# solar_panel_5v.net
KiCad netlist of a schematic drawn in EasyEDA Pro
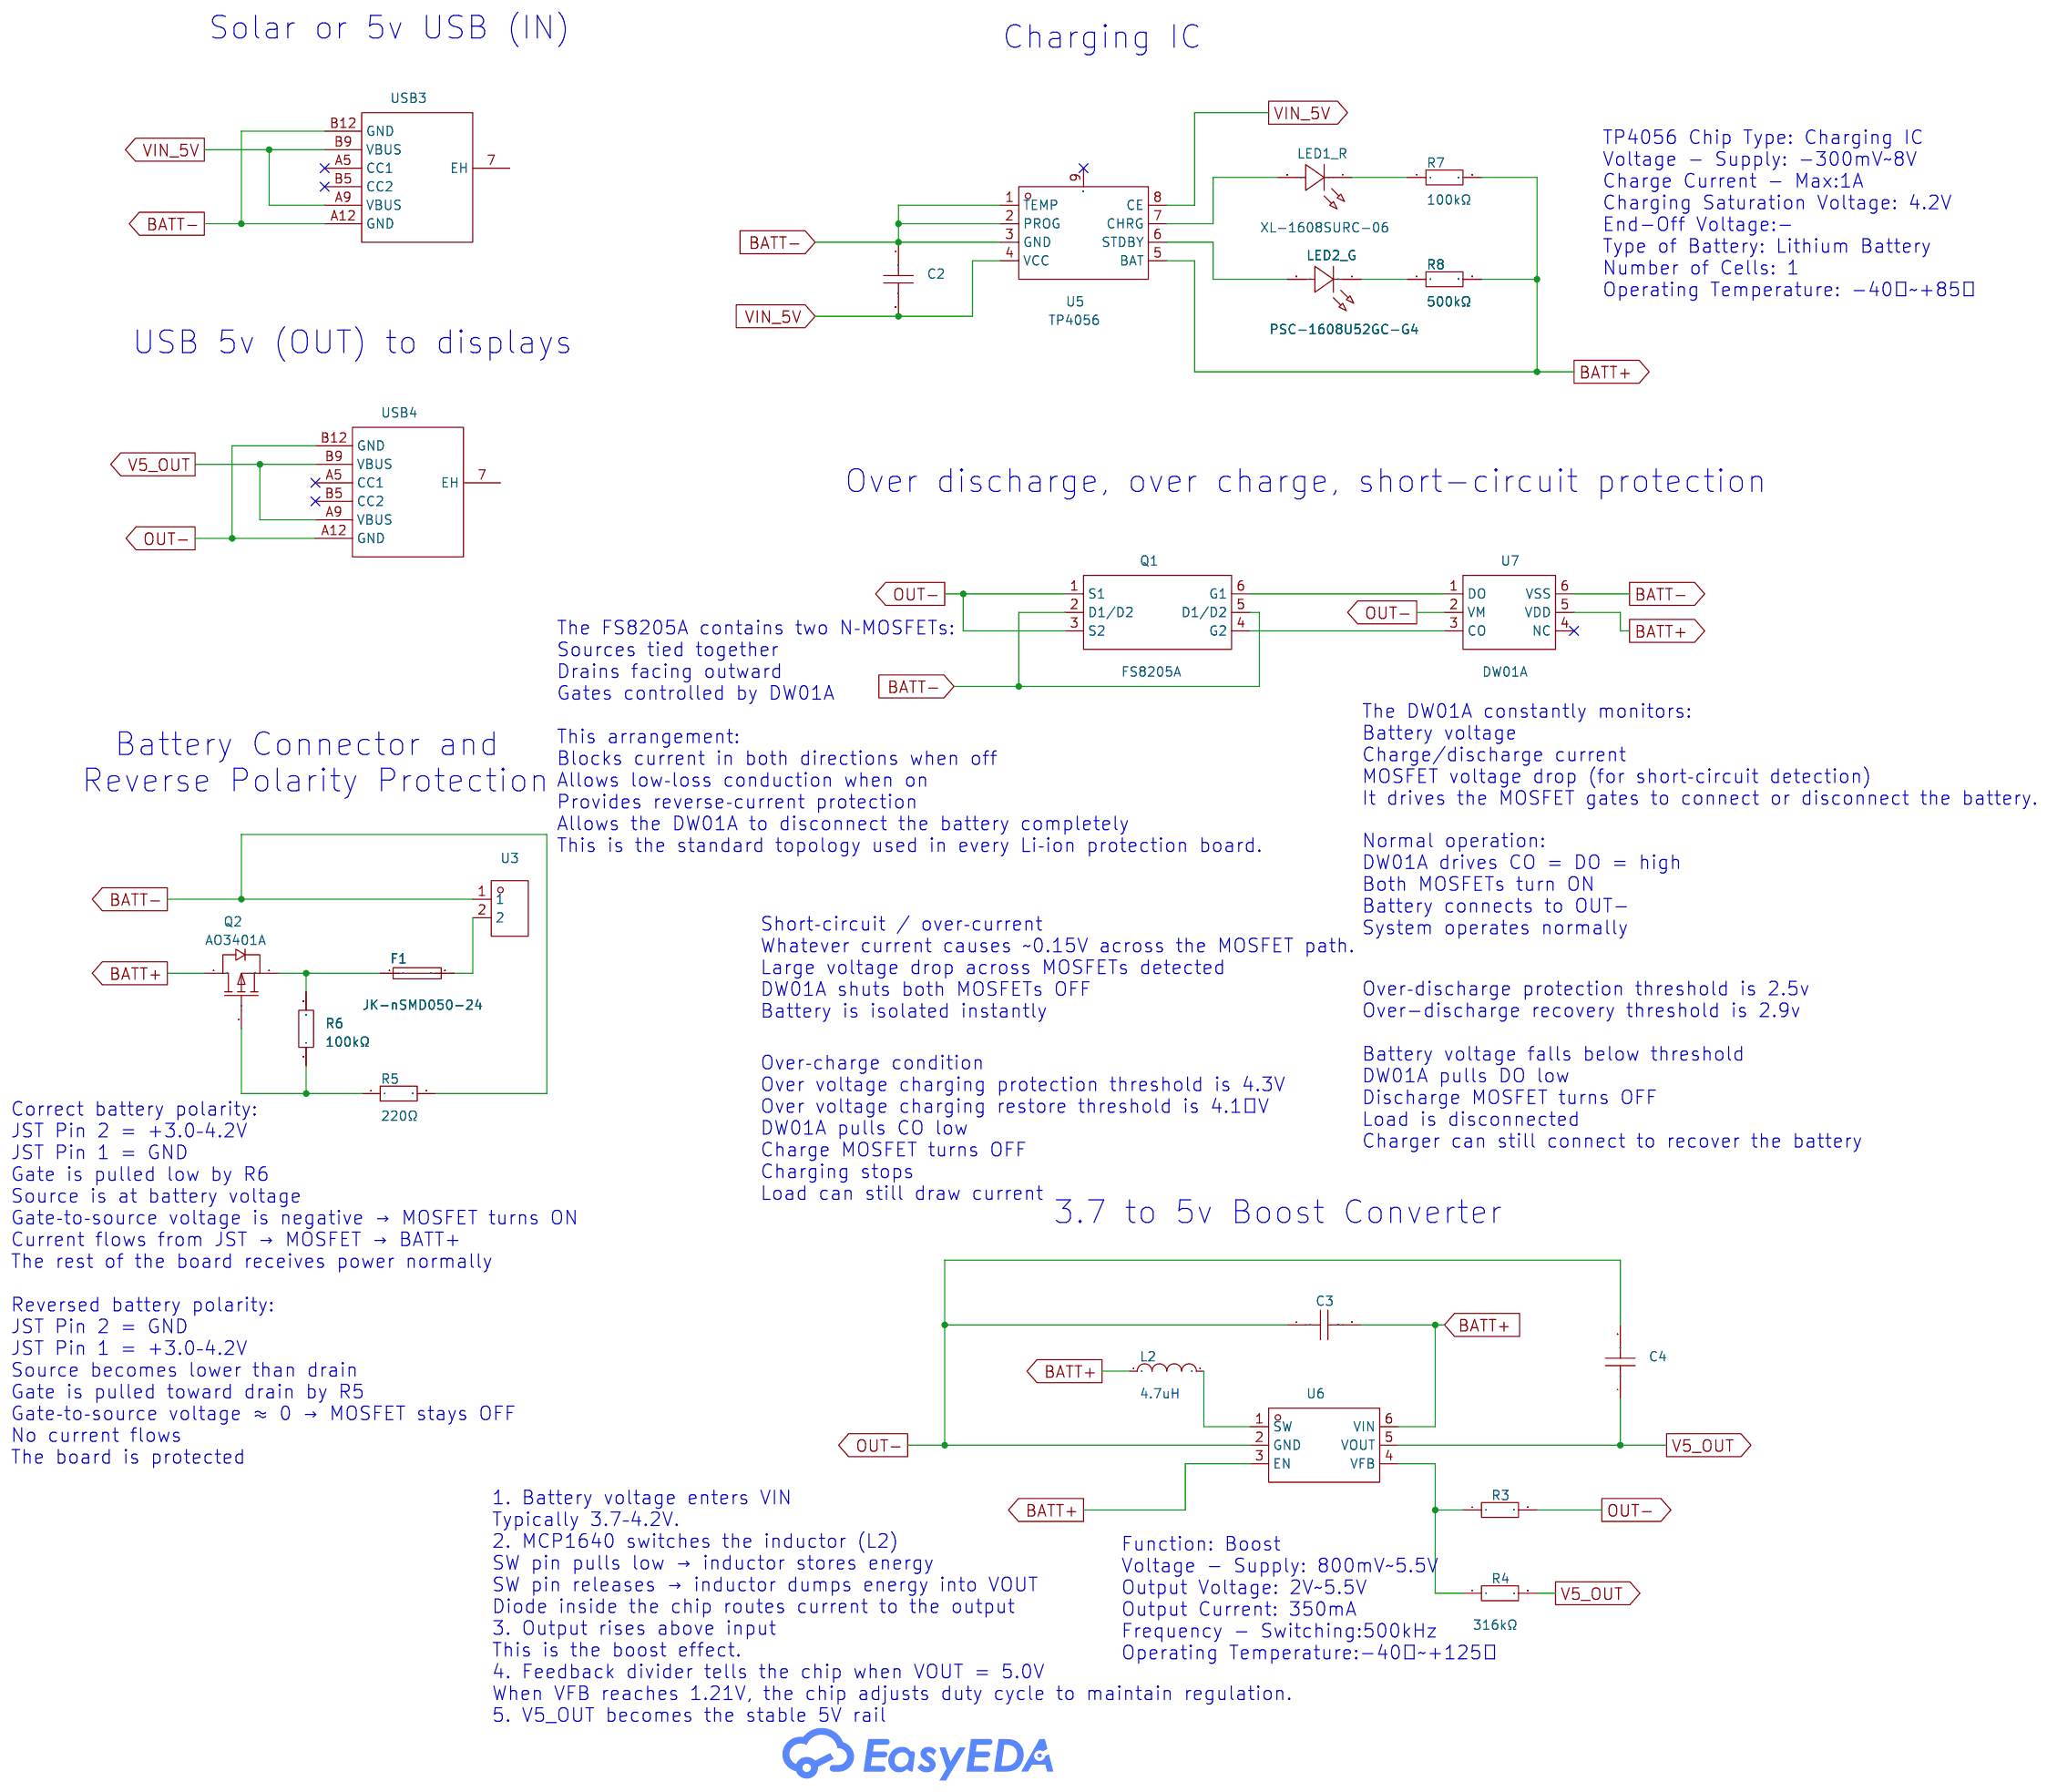
[diagram p0: schematic sheet]

(export (version "E")
  (design (tool "Eeschema 10.0.6"))
  (components
    (comp (ref "C2")
      (value "10uF")
      (footprint "easyedapro:C0603")
      (description "Capacitance:10uF Tolerance:±20% Tolerance:±20% Voltage Rating:6.3V Temperature Coefficient:X5R")
      (fields (field (name "Manufacturer Part") "C0603B106M007T") (field (name "Manufacturer") "IHHEC(禾伸堂)"))
      (libsource (lib "easyedapro") (part "CAP"))
    )
    (comp (ref "C3")
      (value "10uF")
      (footprint "easyedapro:C0603")
      (description "Capacitance:10uF Tolerance:±20% Tolerance:±20% Voltage Rating:6.3V Temperature Coefficient:X5R")
      (fields (field (name "Manufacturer Part") "C0603B106M007T") (field (name "Manufacturer") "IHHEC(禾伸堂)"))
      (libsource (lib "easyedapro") (part "CAP"))
    )
    (comp (ref "C4")
      (value "10uF")
      (footprint "easyedapro:C0603")
      (description "Capacitance:10uF Tolerance:±20% Tolerance:±20% Voltage Rating:6.3V Temperature Coefficient:X5R")
      (fields (field (name "Manufacturer Part") "C0603B106M007T") (field (name "Manufacturer") "IHHEC(禾伸堂)"))
      (libsource (lib "easyedapro") (part "CAP"))
    )
    (comp (ref "F1")
      (value "JK-nSMD050-24")
      (footprint "easyedapro:F1206")
      (fields (field (name "Manufacturer") "JK(金科)"))
      (libsource (lib "easyedapro") (part "JK-NSMD050-24V"))
    )
    (comp (ref "L2")
      (value "4.7uH")
      (footprint "easyedapro:L0805")
      (fields
        (field (name "Manufacturer Part") "CPY201209T-4R7M-NP")
        (field (name "Manufacturer") "Chilisin(奇力新)")
      )
      (libsource (lib "easyedapro") (part "CPY201209T-4R7M-NP"))
    )
    (comp (ref "LED1_R")
      (value "XL-1608SURC-06")
      (footprint "easyedapro:LED0603-RD_RED")
      (fields (field (name "Manufacturer") "XINGLIGHT(成兴光)"))
      (libsource (lib "easyedapro") (part "XL-1608SURC-06"))
    )
    (comp (ref "LED2_G")
      (value "PSC-1608U52GC-G4")
      (footprint "easyedapro:LED0603-RD_GREEN")
      (fields (field (name "Manufacturer") "HONGLITRONIC(鸿利光电)"))
      (libsource (lib "easyedapro") (part "PSC-1608U52GC-G4"))
    )
    (comp (ref "Q1")
      (value "FS8205A")
      (footprint "easyedapro:SOT-23-6_L2.9-W1.6-P0.95-LS2.8-BR")
      (fields (field (name "Manufacturer") "FUXINSEMI(富芯森美)"))
      (libsource (lib "easyedapro") (part "FS8205A_C908265"))
    )
    (comp (ref "Q2")
      (value "AO3401A")
      (footprint "easyedapro:SOT-23_L2.9-W1.3-P1.90-LS2.4-BR")
      (fields (field (name "Manufacturer") "AOS"))
      (libsource (lib "easyedapro") (part "AO3401A"))
    )
    (comp (ref "R3")
      (value "100kΩ")
      (footprint "easyedapro:R0603")
      (fields (field (name "Manufacturer Part") "FRC0603J104 TS") (field (name "Manufacturer") "FOJAN(富捷)"))
      (libsource (lib "easyedapro") (part "Res"))
    )
    (comp (ref "R4")
      (value "316kΩ")
      (footprint "easyedapro:R0603")
      (fields (field (name "Manufacturer Part") "FRC0603F3163TS") (field (name "Manufacturer") "FOJAN(富捷)"))
      (libsource (lib "easyedapro") (part "Res"))
    )
    (comp (ref "R5")
      (value "220Ω")
      (footprint "easyedapro:R0603")
      (fields (field (name "Manufacturer Part") "SCR0603J220R") (field (name "Manufacturer") "VO(翔胜)"))
      (libsource (lib "easyedapro") (part "Res"))
    )
    (comp (ref "R6")
      (value "100kΩ")
      (footprint "easyedapro:R0603")
      (fields (field (name "Manufacturer Part") "FCR0603F100K") (field (name "Manufacturer") "VO(翔胜)"))
      (libsource (lib "easyedapro") (part "Res"))
    )
    (comp (ref "R7")
      (value "100kΩ")
      (footprint "easyedapro:R0603")
      (fields (field (name "Manufacturer Part") "FCR0603F100K") (field (name "Manufacturer") "VO(翔胜)"))
      (libsource (lib "easyedapro") (part "Res"))
    )
    (comp (ref "R8")
      (value "500kΩ")
      (footprint "easyedapro:R0603")
      (fields (field (name "Manufacturer Part") "CR165003F") (field (name "Manufacturer") "Meritek"))
      (libsource (lib "easyedapro") (part "Res"))
    )
    (comp (ref "U3")
      (value "S2B-PH-SM4-TB(LF)(SN)")
      (footprint "easyedapro:CONN-TH_2P-P2.00_2B-PH-KL")
      (fields (field (name "Manufacturer") "JST"))
      (libsource (lib "easyedapro") (part "B2B-PH-KL"))
    )
    (comp (ref "U5")
      (value "TP4056")
      (footprint "easyedapro:ESOP-8_L4.9-W3.9-P1.27-LS6.0-BL-EP-4")
      (fields (field (name "Manufacturer") "YONGYUTAI(永裕泰)"))
      (libsource (lib "easyedapro") (part "TP4056_C20199357"))
    )
    (comp (ref "U6")
      (value "MCP1640BT-I/CHY")
      (footprint "easyedapro:SOT-23-6_L2.9-W1.6-P0.95-LS2.8-BR")
      (fields (field (name "Manufacturer") "MICROCHIP(美国微芯)"))
      (libsource (lib "easyedapro") (part "MCP1640BT-I/CHY"))
    )
    (comp (ref "U7")
      (value "DW01A")
      (footprint "easyedapro:SOT-23-6_L2.9-W1.6-P0.95-LS2.9-BL")
      (fields (field (name "Manufacturer") "Slkor(萨科微)"))
      (libsource (lib "easyedapro") (part "DW01A_C42380662"))
    )
    (comp (ref "USB3")
      (value "TYPE-C 6P")
      (footprint "easyedapro:TYPE-C-SMD_TYPE-C-6P_1")
      (fields (field (name "Manufacturer") "SHOU HAN(首韩)"))
      (libsource (lib "easyedapro") (part "TYPE-C 6P"))
    )
    (comp (ref "USB4")
      (value "TYPE-C 6P")
      (footprint "easyedapro:TYPE-C-SMD_TYPE-C-6P_1")
      (fields (field (name "Manufacturer") "SHOU HAN(首韩)"))
      (libsource (lib "easyedapro") (part "TYPE-C 6P"))
    )
  )
  (nets
    (net (code "1") (name "BATT+") (class "Default")
      (node (ref "C3") (pin "2") (pinfunction "2_2") (pintype "input"))
      (node (ref "L2") (pin "1") (pinfunction "1_1") (pintype "unspecified"))
      (node (ref "Q2") (pin "3") (pinfunction "D_3") (pintype "unspecified"))
      (node (ref "R7") (pin "2") (pinfunction "2_2") (pintype "input"))
      (node (ref "R8") (pin "2") (pinfunction "2_2") (pintype "input"))
      (node (ref "U5") (pin "5") (pinfunction "BAT_5") (pintype "unspecified"))
      (node (ref "U6") (pin "3") (pinfunction "EN_3") (pintype "input"))
      (node (ref "U6") (pin "6") (pinfunction "VIN_6") (pintype "input"))
      (node (ref "U7") (pin "5") (pinfunction "VDD_5") (pintype "unspecified"))
    )
    (net (code "2") (name "BATT-") (class "Default")
      (node (ref "C2") (pin "1") (pinfunction "1_1") (pintype "input"))
      (node (ref "Q1") (pin "2") (pinfunction "D1/D2_2") (pintype "unspecified"))
      (node (ref "Q1") (pin "5") (pinfunction "D1/D2_5") (pintype "unspecified"))
      (node (ref "R5") (pin "2") (pinfunction "2_2") (pintype "input"))
      (node (ref "U3") (pin "1") (pinfunction "1_1") (pintype "unspecified"))
      (node (ref "U5") (pin "1") (pinfunction "TEMP_1") (pintype "unspecified"))
      (node (ref "U5") (pin "2") (pinfunction "PROG_2") (pintype "unspecified"))
      (node (ref "U5") (pin "3") (pinfunction "GND_3") (pintype "unspecified"))
      (node (ref "U7") (pin "6") (pinfunction "VSS_6") (pintype "unspecified"))
      (node (ref "USB3") (pin "A12") (pinfunction "GND_A12") (pintype "unspecified"))
      (node (ref "USB3") (pin "B12") (pinfunction "GND_B12") (pintype "unspecified"))
    )
    (net (code "3") (name "Net-(F1-Pad2)") (class "Default")
      (node (ref "F1") (pin "2") (pinfunction "2_2") (pintype "unspecified"))
      (node (ref "U3") (pin "2") (pinfunction "2_2") (pintype "unspecified"))
    )
    (net (code "4") (name "Net-(LED1_R-A)") (class "Default")
      (node (ref "LED1_R") (pin "2") (pinfunction "A_2") (pintype "unspecified"))
      (node (ref "U5") (pin "7") (pinfunction "CHRG_7") (pintype "unspecified"))
    )
    (net (code "5") (name "Net-(LED1_R-K)") (class "Default")
      (node (ref "LED1_R") (pin "1") (pinfunction "K_1") (pintype "unspecified"))
      (node (ref "R7") (pin "1") (pinfunction "1_1") (pintype "input"))
    )
    (net (code "6") (name "Net-(LED2_G-A)") (class "Default")
      (node (ref "LED2_G") (pin "2") (pinfunction "A_2") (pintype "unspecified"))
      (node (ref "U5") (pin "6") (pinfunction "STDBY_6") (pintype "unspecified"))
    )
    (net (code "7") (name "Net-(LED2_G-K)") (class "Default")
      (node (ref "LED2_G") (pin "1") (pinfunction "K_1") (pintype "unspecified"))
      (node (ref "R8") (pin "1") (pinfunction "1_1") (pintype "input"))
    )
    (net (code "8") (name "Net-(Q1-G1)") (class "Default")
      (node (ref "Q1") (pin "6") (pinfunction "G1_6") (pintype "unspecified"))
      (node (ref "U7") (pin "1") (pinfunction "DO_1") (pintype "unspecified"))
    )
    (net (code "9") (name "Net-(Q1-G2)") (class "Default")
      (node (ref "Q1") (pin "4") (pinfunction "G2_4") (pintype "unspecified"))
      (node (ref "U7") (pin "3") (pinfunction "CO_3") (pintype "unspecified"))
    )
    (net (code "10") (name "Net-(Q2-G)") (class "Default")
      (node (ref "Q2") (pin "1") (pinfunction "G_1") (pintype "unspecified"))
      (node (ref "R5") (pin "1") (pinfunction "1_1") (pintype "input"))
      (node (ref "R6") (pin "1") (pinfunction "1_1") (pintype "input"))
    )
    (net (code "11") (name "Net-(Q2-S)") (class "Default")
      (node (ref "F1") (pin "1") (pinfunction "1_1") (pintype "unspecified"))
      (node (ref "Q2") (pin "2") (pinfunction "S_2") (pintype "unspecified"))
      (node (ref "R6") (pin "2") (pinfunction "2_2") (pintype "input"))
    )
    (net (code "12") (name "Net-(U6-SW)") (class "Default")
      (node (ref "L2") (pin "2") (pinfunction "2_2") (pintype "unspecified"))
      (node (ref "U6") (pin "1") (pinfunction "SW_1") (pintype "input"))
    )
    (net (code "13") (name "Net-(U6-VFB)") (class "Default")
      (node (ref "R3") (pin "1") (pinfunction "1_1") (pintype "input"))
      (node (ref "R4") (pin "1") (pinfunction "1_1") (pintype "input"))
      (node (ref "U6") (pin "4") (pinfunction "VFB_4") (pintype "input"))
    )
    (net (code "14") (name "OUT-") (class "Default")
      (node (ref "C3") (pin "1") (pinfunction "1_1") (pintype "input"))
      (node (ref "C4") (pin "2") (pinfunction "2_2") (pintype "input"))
      (node (ref "Q1") (pin "1") (pinfunction "S1_1") (pintype "unspecified"))
      (node (ref "Q1") (pin "3") (pinfunction "S2_3") (pintype "unspecified"))
      (node (ref "R3") (pin "2") (pinfunction "2_2") (pintype "input"))
      (node (ref "U6") (pin "2") (pinfunction "GND_2") (pintype "input"))
      (node (ref "U7") (pin "2") (pinfunction "VM_2") (pintype "unspecified"))
      (node (ref "USB4") (pin "A12") (pinfunction "GND_A12") (pintype "unspecified"))
      (node (ref "USB4") (pin "B12") (pinfunction "GND_B12") (pintype "unspecified"))
    )
    (net (code "15") (name "V5_OUT") (class "Default")
      (node (ref "C4") (pin "1") (pinfunction "1_1") (pintype "input"))
      (node (ref "R4") (pin "2") (pinfunction "2_2") (pintype "input"))
      (node (ref "U6") (pin "5") (pinfunction "VOUT_5") (pintype "input"))
      (node (ref "USB4") (pin "A9") (pinfunction "VBUS_A9") (pintype "unspecified"))
      (node (ref "USB4") (pin "B9") (pinfunction "VBUS_B9") (pintype "unspecified"))
    )
    (net (code "16") (name "VIN_5V") (class "Default")
      (node (ref "C2") (pin "2") (pinfunction "2_2") (pintype "input"))
      (node (ref "U5") (pin "4") (pinfunction "VCC_4") (pintype "unspecified"))
      (node (ref "U5") (pin "8") (pinfunction "CE_8") (pintype "unspecified"))
      (node (ref "USB3") (pin "A9") (pinfunction "VBUS_A9") (pintype "unspecified"))
      (node (ref "USB3") (pin "B9") (pinfunction "VBUS_B9") (pintype "unspecified"))
    )
    (net (code "17") (name "unconnected-(U5-PAD-Pad9)") (class "Default")
      (node (ref "U5") (pin "9") (pinfunction "PAD_9") (pintype "unspecified+no_connect"))
    )
    (net (code "18") (name "unconnected-(U7-NC-Pad4)") (class "Default")
      (node (ref "U7") (pin "4") (pinfunction "NC_4") (pintype "unspecified+no_connect"))
    )
    (net (code "19") (name "unconnected-(USB3-CC1-PadA5)") (class "Default")
      (node (ref "USB3") (pin "A5") (pinfunction "CC1_A5") (pintype "unspecified+no_connect"))
    )
    (net (code "20") (name "unconnected-(USB3-CC2-PadB5)") (class "Default")
      (node (ref "USB3") (pin "B5") (pinfunction "CC2_B5") (pintype "unspecified+no_connect"))
    )
    (net (code "21") (name "unconnected-(USB3-EH-Pad7)") (class "Default")
      (node (ref "USB3") (pin "7") (pinfunction "EH_7") (pintype "unspecified"))
    )
    (net (code "22") (name "unconnected-(USB4-CC1-PadA5)") (class "Default")
      (node (ref "USB4") (pin "A5") (pinfunction "CC1_A5") (pintype "unspecified+no_connect"))
    )
    (net (code "23") (name "unconnected-(USB4-CC2-PadB5)") (class "Default")
      (node (ref "USB4") (pin "B5") (pinfunction "CC2_B5") (pintype "unspecified+no_connect"))
    )
    (net (code "24") (name "unconnected-(USB4-EH-Pad7)") (class "Default")
      (node (ref "USB4") (pin "7") (pinfunction "EH_7") (pintype "unspecified"))
    )
  )
)
